# MOT_DRV.net
KiCad netlist of a schematic drawn in Altium Designer
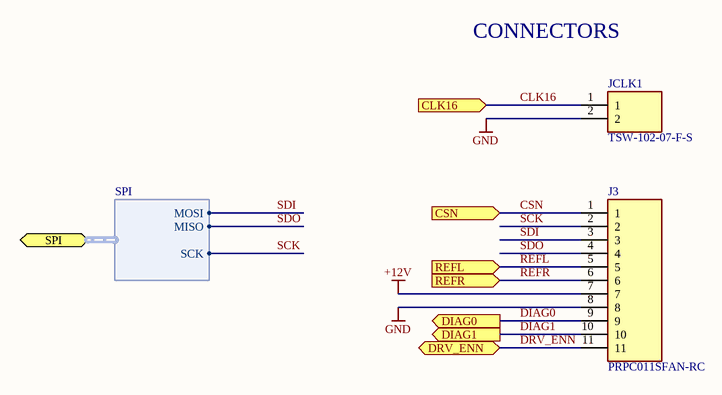
[diagram p0: MOT_DRV.SchDoc]

(export (version "E")
  (design (tool "Eeschema 10.0.6"))
  (components
    (comp (ref "J3")
      (value "PRPC011SFAN-RC")
      (footprint "HDRV11W64P254_1X11_2794X254X1058P")
      (description "Connector")
      (libsource (lib "*") (part "PRPC011SFAN-RC"))
    )
    (comp (ref "JCLK1")
      (value "TSW-102-07-F-S")
      (footprint "HDRV2W64P254_1X2_508X241X838P")
      (description "Connector")
      (fields (field (name "MOUSER PART NUMBER") "200-TSW10207FS") (field (name "RS PART NUMBER") "1557967"))
      (libsource (lib "*") (part "TSW-102-07-F-S"))
    )
  )
  (nets
    (net (code "2") (name "+12V") (class "Default")
      (node (ref "J3") (pin "7") (pinfunction "7_7") (pintype "passive"))
    )
    (net (code "3") (name "/CLK16") (class "Default")
      (node (ref "JCLK1") (pin "1") (pinfunction "1_1") (pintype "passive"))
    )
    (net (code "4") (name "/CSN") (class "Default")
      (node (ref "J3") (pin "1") (pinfunction "1_1") (pintype "passive"))
    )
    (net (code "5") (name "/DIAG0") (class "Default")
      (node (ref "J3") (pin "9") (pinfunction "9_9") (pintype "passive"))
    )
    (net (code "6") (name "/DIAG1") (class "Default")
      (node (ref "J3") (pin "10") (pinfunction "10_10") (pintype "passive"))
    )
    (net (code "7") (name "/DRV_ENN") (class "Default")
      (node (ref "J3") (pin "11") (pinfunction "11_11") (pintype "passive"))
    )
    (net (code "8") (name "/REFL") (class "Default")
      (node (ref "J3") (pin "5") (pinfunction "5_5") (pintype "passive"))
    )
    (net (code "9") (name "/REFR") (class "Default")
      (node (ref "J3") (pin "6") (pinfunction "6_6") (pintype "passive"))
    )
    (net (code "10") (name "/SCK") (class "Default")
      (node (ref "J3") (pin "2") (pinfunction "2_2") (pintype "passive"))
    )
    (net (code "11") (name "/SDI") (class "Default")
      (node (ref "J3") (pin "3") (pinfunction "3_3") (pintype "passive"))
    )
    (net (code "12") (name "/SDO") (class "Default")
      (node (ref "J3") (pin "4") (pinfunction "4_4") (pintype "passive"))
    )
    (net (code "14") (name "GND") (class "Default")
      (node (ref "J3") (pin "8") (pinfunction "8_8") (pintype "passive"))
      (node (ref "JCLK1") (pin "2") (pinfunction "2_2") (pintype "passive"))
    )
  )
)
